# H_BRIDGE_Driver.net
KiCad netlist of a schematic drawn in Altium Designer
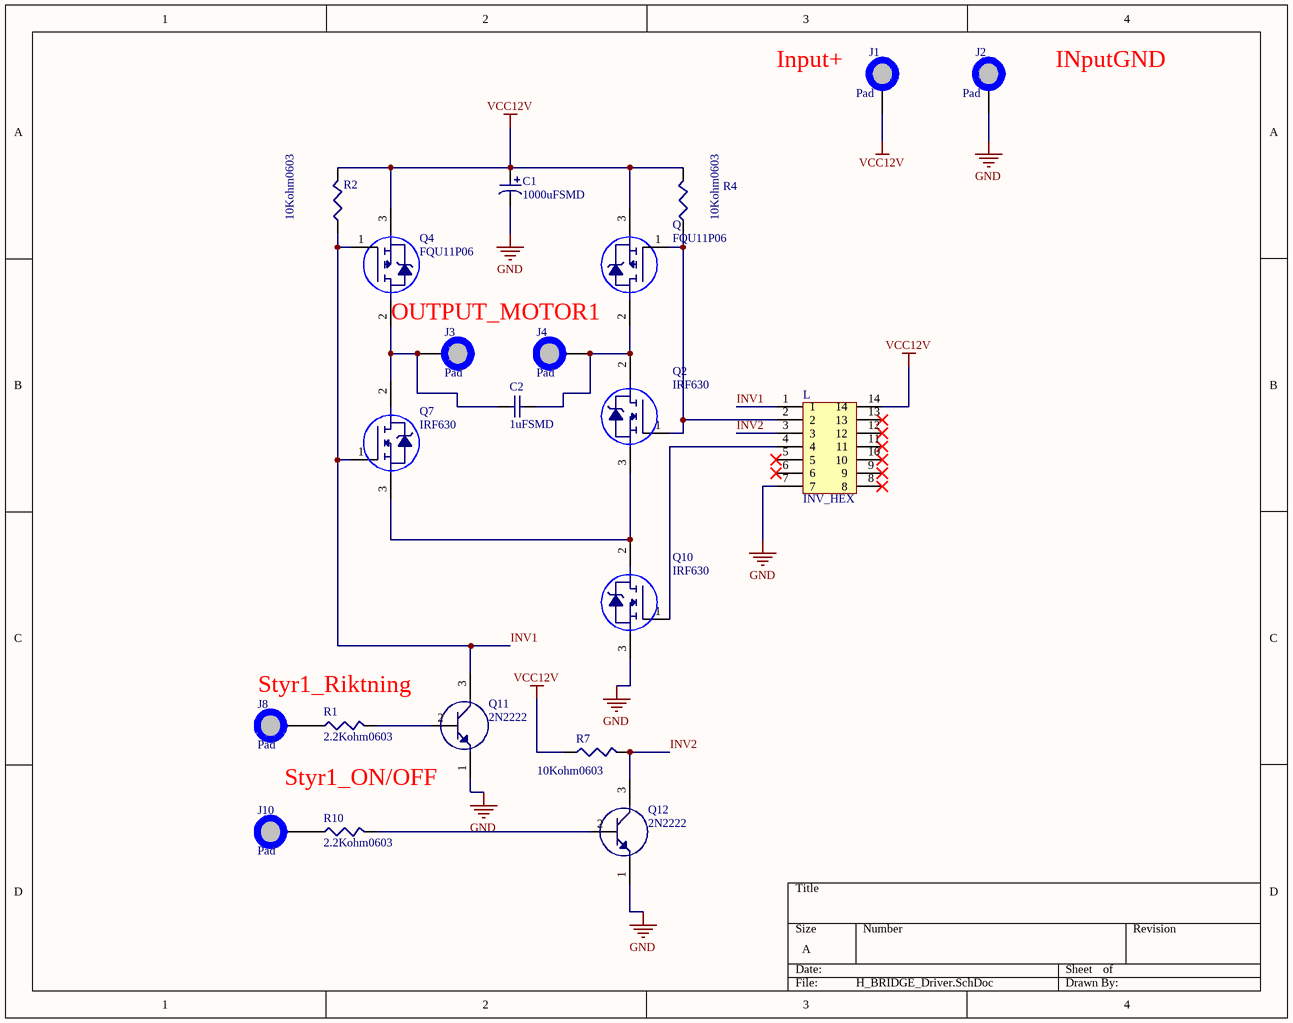
[diagram p0: H_BRIDGE_Driver.SchDoc]

(export (version "E")
  (design (tool "Eeschema 10.0.6"))
  (components
    (comp (ref "C1")
      (value "1000uFSMD")
      (footprint "SMDaliminium-elektrolyt")
      (fields
        (field (name "MANUFACTURER") "Würth Elektronik (Wuerth Elektronik)")
        (field (name "MANUFACTURER PART NUMBER") "865060462010")
        (field (name "TOLERANCE") "±20%")
      )
      (libsource (lib "H_BRIDGE_Driver") (part "865060462010"))
    )
    (comp (ref "C2")
      (value "1uFSMD")
      (footprint "C0805")
      (description "Cap Ceramic 1uF 25V Y5V -20% to 80% SMD 0805 85C Plastic T/R")
      (fields
        (field (name "MANUFACTURER") "Walsin Technologies")
        (field (name "MANUFACTURER PART NUMBER") "0805F105Z250CT")
      )
      (libsource (lib "H_BRIDGE_Driver") (part "0805F105Z250CT"))
    )
    (comp (ref "J1")
      (value "Pad")
      (footprint "PAD_WITH_HOLE_4MMx1.5MM")
      (libsource (lib "H_BRIDGE_Driver") (part "Hole"))
    )
    (comp (ref "J2")
      (value "Pad")
      (footprint "PAD_WITH_HOLE_4MMx1.5MM")
      (libsource (lib "H_BRIDGE_Driver") (part "Hole"))
    )
    (comp (ref "J3")
      (value "Pad")
      (footprint "PAD_WITH_HOLE_4MMx1.5MM")
      (libsource (lib "H_BRIDGE_Driver") (part "Hole"))
    )
    (comp (ref "J4")
      (value "Pad")
      (footprint "PAD_WITH_HOLE_4MMx1.5MM")
      (libsource (lib "H_BRIDGE_Driver") (part "Hole"))
    )
    (comp (ref "J8")
      (value "Pad")
      (footprint "PAD_WITH_HOLE_4MMx1.5MM")
      (libsource (lib "H_BRIDGE_Driver") (part "Hole"))
    )
    (comp (ref "J10")
      (value "Pad")
      (footprint "PAD_WITH_HOLE_4MMx1.5MM")
      (libsource (lib "H_BRIDGE_Driver") (part "Hole"))
    )
    (comp (ref "L")
      (value "INV_HEX")
      (footprint "DIP14")
      (description "IC, HEX INVERTER, 4000 CMOS, 16DIP")
      (fields
        (field (name "MANUFACTURER") "Texas Instruments (TI)")
        (field (name "MANUFACTURER PART NUMBER") "CD40106BE")
      )
      (libsource (lib "H_BRIDGE_Driver") (part "CD40106BE"))
    )
    (comp (ref "Q")
      (value "FQU11P06")
      (footprint "I-PAK")
      (fields (field (name "MANUFACTURER") "Fairchild Semiconductor"))
      (libsource (lib "H_BRIDGE_Driver") (part "FQU11P06"))
    )
    (comp (ref "Q2")
      (value "IRF630")
      (footprint "TO-220WithHeatSink")
      (description "MOSFET N-CH 200V 9A TO-220")
      (fields (field (name "MANUFACTURER") "STMicroelectronics"))
      (libsource (lib "H_BRIDGE_Driver") (part "IRF630"))
    )
    (comp (ref "Q4")
      (value "FQU11P06")
      (footprint "I-PAK")
      (fields (field (name "MANUFACTURER") "Fairchild Semiconductor"))
      (libsource (lib "H_BRIDGE_Driver") (part "FQU11P06"))
    )
    (comp (ref "Q7")
      (value "IRF630")
      (footprint "TO-220WithHeatSink")
      (description "MOSFET N-CH 200V 9A TO-220")
      (fields (field (name "MANUFACTURER") "STMicroelectronics"))
      (libsource (lib "H_BRIDGE_Driver") (part "IRF630"))
    )
    (comp (ref "Q10")
      (value "IRF630")
      (footprint "TO-220WithHeatSink")
      (description "MOSFET N-CH 200V 9A TO-220")
      (fields (field (name "MANUFACTURER") "STMicroelectronics"))
      (libsource (lib "H_BRIDGE_Driver") (part "IRF630"))
    )
    (comp (ref "Q11")
      (value "2N2222")
      (footprint "BJT2N2222")
      (fields (field (name "MANUFACTURER") "Multicomp"))
      (libsource (lib "H_BRIDGE_Driver") (part "2N2222"))
    )
    (comp (ref "Q12")
      (value "2N2222")
      (footprint "BJT2N2222")
      (fields (field (name "MANUFACTURER") "Multicomp"))
      (libsource (lib "H_BRIDGE_Driver") (part "2N2222"))
    )
    (comp (ref "R1")
      (value "2.2Kohm0603")
      (footprint "R0603")
      (description "RES SMD 2.2K OHM 1% 1/10W 0603")
      (fields
        (field (name "MANUFACTURER") "Yageo")
        (field (name "MANUFACTURER PART NUMBER") "RC0603FR-072K2L")
      )
      (libsource (lib "H_BRIDGE_Driver") (part "RC0603FR-072K2L"))
    )
    (comp (ref "R2")
      (value "10Kohm0603")
      (footprint "R0603")
      (description "YAGEO         RC0603FR-0710KL             RES, THICK FILM, 10K, 1%, 0.1W, 0603")
      (fields
        (field (name "MANUFACTURER") "Yageo")
        (field (name "MANUFACTURER PART NUMBER") "RC0603FR-0710KL")
      )
      (libsource (lib "H_BRIDGE_Driver") (part "RC0603FR-0710KL"))
    )
    (comp (ref "R4")
      (value "10Kohm0603")
      (footprint "R0603")
      (description "YAGEO         RC0603FR-0710KL             RES, THICK FILM, 10K, 1%, 0.1W, 0603")
      (fields
        (field (name "MANUFACTURER") "Yageo")
        (field (name "MANUFACTURER PART NUMBER") "RC0603FR-0710KL")
      )
      (libsource (lib "H_BRIDGE_Driver") (part "RC0603FR-0710KL"))
    )
    (comp (ref "R7")
      (value "10Kohm0603")
      (footprint "R0603")
      (description "YAGEO         RC0603FR-0710KL             RES, THICK FILM, 10K, 1%, 0.1W, 0603")
      (fields
        (field (name "MANUFACTURER") "Yageo")
        (field (name "MANUFACTURER PART NUMBER") "RC0603FR-0710KL")
      )
      (libsource (lib "H_BRIDGE_Driver") (part "RC0603FR-0710KL"))
    )
    (comp (ref "R10")
      (value "2.2Kohm0603")
      (footprint "R0603")
      (description "RES SMD 2.2K OHM 1% 1/10W 0603")
      (fields
        (field (name "MANUFACTURER") "Yageo")
        (field (name "MANUFACTURER PART NUMBER") "RC0603FR-072K2L")
      )
      (libsource (lib "H_BRIDGE_Driver") (part "RC0603FR-072K2L"))
    )
  )
  (nets
    (net (code "1") (name "/INV1") (class "Default")
      (node (ref "L") (pin "1") (pinfunction "1_1") (pintype "passive"))
      (node (ref "Q11") (pin "3") (pinfunction "3_3") (pintype "passive"))
      (node (ref "Q4") (pin "1") (pinfunction "1_1") (pintype "passive"))
      (node (ref "Q7") (pin "1") (pinfunction "1_1") (pintype "passive"))
      (node (ref "R2") (pin "1") (pinfunction "1_1") (pintype "passive"))
    )
    (net (code "2") (name "/INV2") (class "Default")
      (node (ref "L") (pin "3") (pinfunction "3_3") (pintype "passive"))
      (node (ref "Q12") (pin "3") (pinfunction "3_3") (pintype "passive"))
      (node (ref "R7") (pin "2") (pinfunction "2_2") (pintype "passive"))
    )
    (net (code "3") (name "GND") (class "Default")
      (node (ref "C1") (pin "2") (pinfunction "2_2") (pintype "passive"))
      (node (ref "J2") (pin "1") (pinfunction "1_1") (pintype "passive"))
      (node (ref "L") (pin "7") (pinfunction "7_7") (pintype "passive"))
      (node (ref "Q10") (pin "3") (pinfunction "3_3") (pintype "passive"))
      (node (ref "Q11") (pin "1") (pinfunction "1_1") (pintype "passive"))
      (node (ref "Q12") (pin "1") (pinfunction "1_1") (pintype "passive"))
    )
    (net (code "4") (name "Net-(C2-Pad1)") (class "Default")
      (node (ref "C2") (pin "1") (pinfunction "1_1") (pintype "passive"))
      (node (ref "J3") (pin "1") (pinfunction "1_1") (pintype "passive"))
      (node (ref "Q4") (pin "2") (pinfunction "2_2") (pintype "passive"))
      (node (ref "Q7") (pin "2") (pinfunction "2_2") (pintype "passive"))
    )
    (net (code "5") (name "Net-(C2-Pad2)") (class "Default")
      (node (ref "C2") (pin "2") (pinfunction "2_2") (pintype "passive"))
      (node (ref "J4") (pin "1") (pinfunction "1_1") (pintype "passive"))
      (node (ref "Q") (pin "2") (pinfunction "2_2") (pintype "passive"))
      (node (ref "Q2") (pin "2") (pinfunction "2_2") (pintype "passive"))
    )
    (net (code "6") (name "Net-(J8-Pad1)") (class "Default")
      (node (ref "J8") (pin "1") (pinfunction "1_1") (pintype "passive"))
      (node (ref "R1") (pin "1") (pinfunction "1_1") (pintype "passive"))
    )
    (net (code "7") (name "Net-(J10-Pad1)") (class "Default")
      (node (ref "J10") (pin "1") (pinfunction "1_1") (pintype "passive"))
      (node (ref "R10") (pin "1") (pinfunction "1_1") (pintype "passive"))
    )
    (net (code "8") (name "Net-(L-Pad2)") (class "Default")
      (node (ref "L") (pin "2") (pinfunction "2_2") (pintype "passive"))
      (node (ref "Q") (pin "1") (pinfunction "1_1") (pintype "passive"))
      (node (ref "Q2") (pin "1") (pinfunction "1_1") (pintype "passive"))
      (node (ref "R4") (pin "1") (pinfunction "1_1") (pintype "passive"))
    )
    (net (code "9") (name "Net-(L-Pad4)") (class "Default")
      (node (ref "L") (pin "4") (pinfunction "4_4") (pintype "passive"))
      (node (ref "Q10") (pin "1") (pinfunction "1_1") (pintype "passive"))
    )
    (net (code "10") (name "Net-(Q10-Pad2)") (class "Default")
      (node (ref "Q10") (pin "2") (pinfunction "2_2") (pintype "passive"))
      (node (ref "Q2") (pin "3") (pinfunction "3_3") (pintype "passive"))
      (node (ref "Q7") (pin "3") (pinfunction "3_3") (pintype "passive"))
    )
    (net (code "11") (name "Net-(Q11-Pad2)") (class "Default")
      (node (ref "Q11") (pin "2") (pinfunction "2_2") (pintype "passive"))
      (node (ref "R1") (pin "2") (pinfunction "2_2") (pintype "passive"))
    )
    (net (code "12") (name "Net-(Q12-Pad2)") (class "Default")
      (node (ref "Q12") (pin "2") (pinfunction "2_2") (pintype "passive"))
      (node (ref "R10") (pin "2") (pinfunction "2_2") (pintype "passive"))
    )
    (net (code "13") (name "VCC12V") (class "Default")
      (node (ref "C1") (pin "1") (pinfunction "1_1") (pintype "passive"))
      (node (ref "J1") (pin "1") (pinfunction "1_1") (pintype "passive"))
      (node (ref "L") (pin "14") (pinfunction "14_14") (pintype "passive"))
      (node (ref "Q") (pin "3") (pinfunction "3_3") (pintype "passive"))
      (node (ref "Q4") (pin "3") (pinfunction "3_3") (pintype "passive"))
      (node (ref "R2") (pin "2") (pinfunction "2_2") (pintype "passive"))
      (node (ref "R4") (pin "2") (pinfunction "2_2") (pintype "passive"))
      (node (ref "R7") (pin "1") (pinfunction "1_1") (pintype "passive"))
    )
    (net (code "14") (name "unconnected-(L-Pad5)") (class "Default")
      (node (ref "L") (pin "5") (pinfunction "5_5") (pintype "passive+no_connect"))
    )
    (net (code "15") (name "unconnected-(L-Pad6)") (class "Default")
      (node (ref "L") (pin "6") (pinfunction "6_6") (pintype "passive+no_connect"))
    )
    (net (code "16") (name "unconnected-(L-Pad8)") (class "Default")
      (node (ref "L") (pin "8") (pinfunction "8_8") (pintype "passive+no_connect"))
    )
    (net (code "17") (name "unconnected-(L-Pad9)") (class "Default")
      (node (ref "L") (pin "9") (pinfunction "9_9") (pintype "passive+no_connect"))
    )
    (net (code "18") (name "unconnected-(L-Pad10)") (class "Default")
      (node (ref "L") (pin "10") (pinfunction "10_10") (pintype "passive+no_connect"))
    )
    (net (code "19") (name "unconnected-(L-Pad11)") (class "Default")
      (node (ref "L") (pin "11") (pinfunction "11_11") (pintype "passive+no_connect"))
    )
    (net (code "20") (name "unconnected-(L-Pad12)") (class "Default")
      (node (ref "L") (pin "12") (pinfunction "12_12") (pintype "passive+no_connect"))
    )
    (net (code "21") (name "unconnected-(L-Pad13)") (class "Default")
      (node (ref "L") (pin "13") (pinfunction "13_13") (pintype "passive+no_connect"))
    )
  )
)
